# rx5808_vTup_0_4.net
KiCad netlist of a schematic drawn in EAGLE
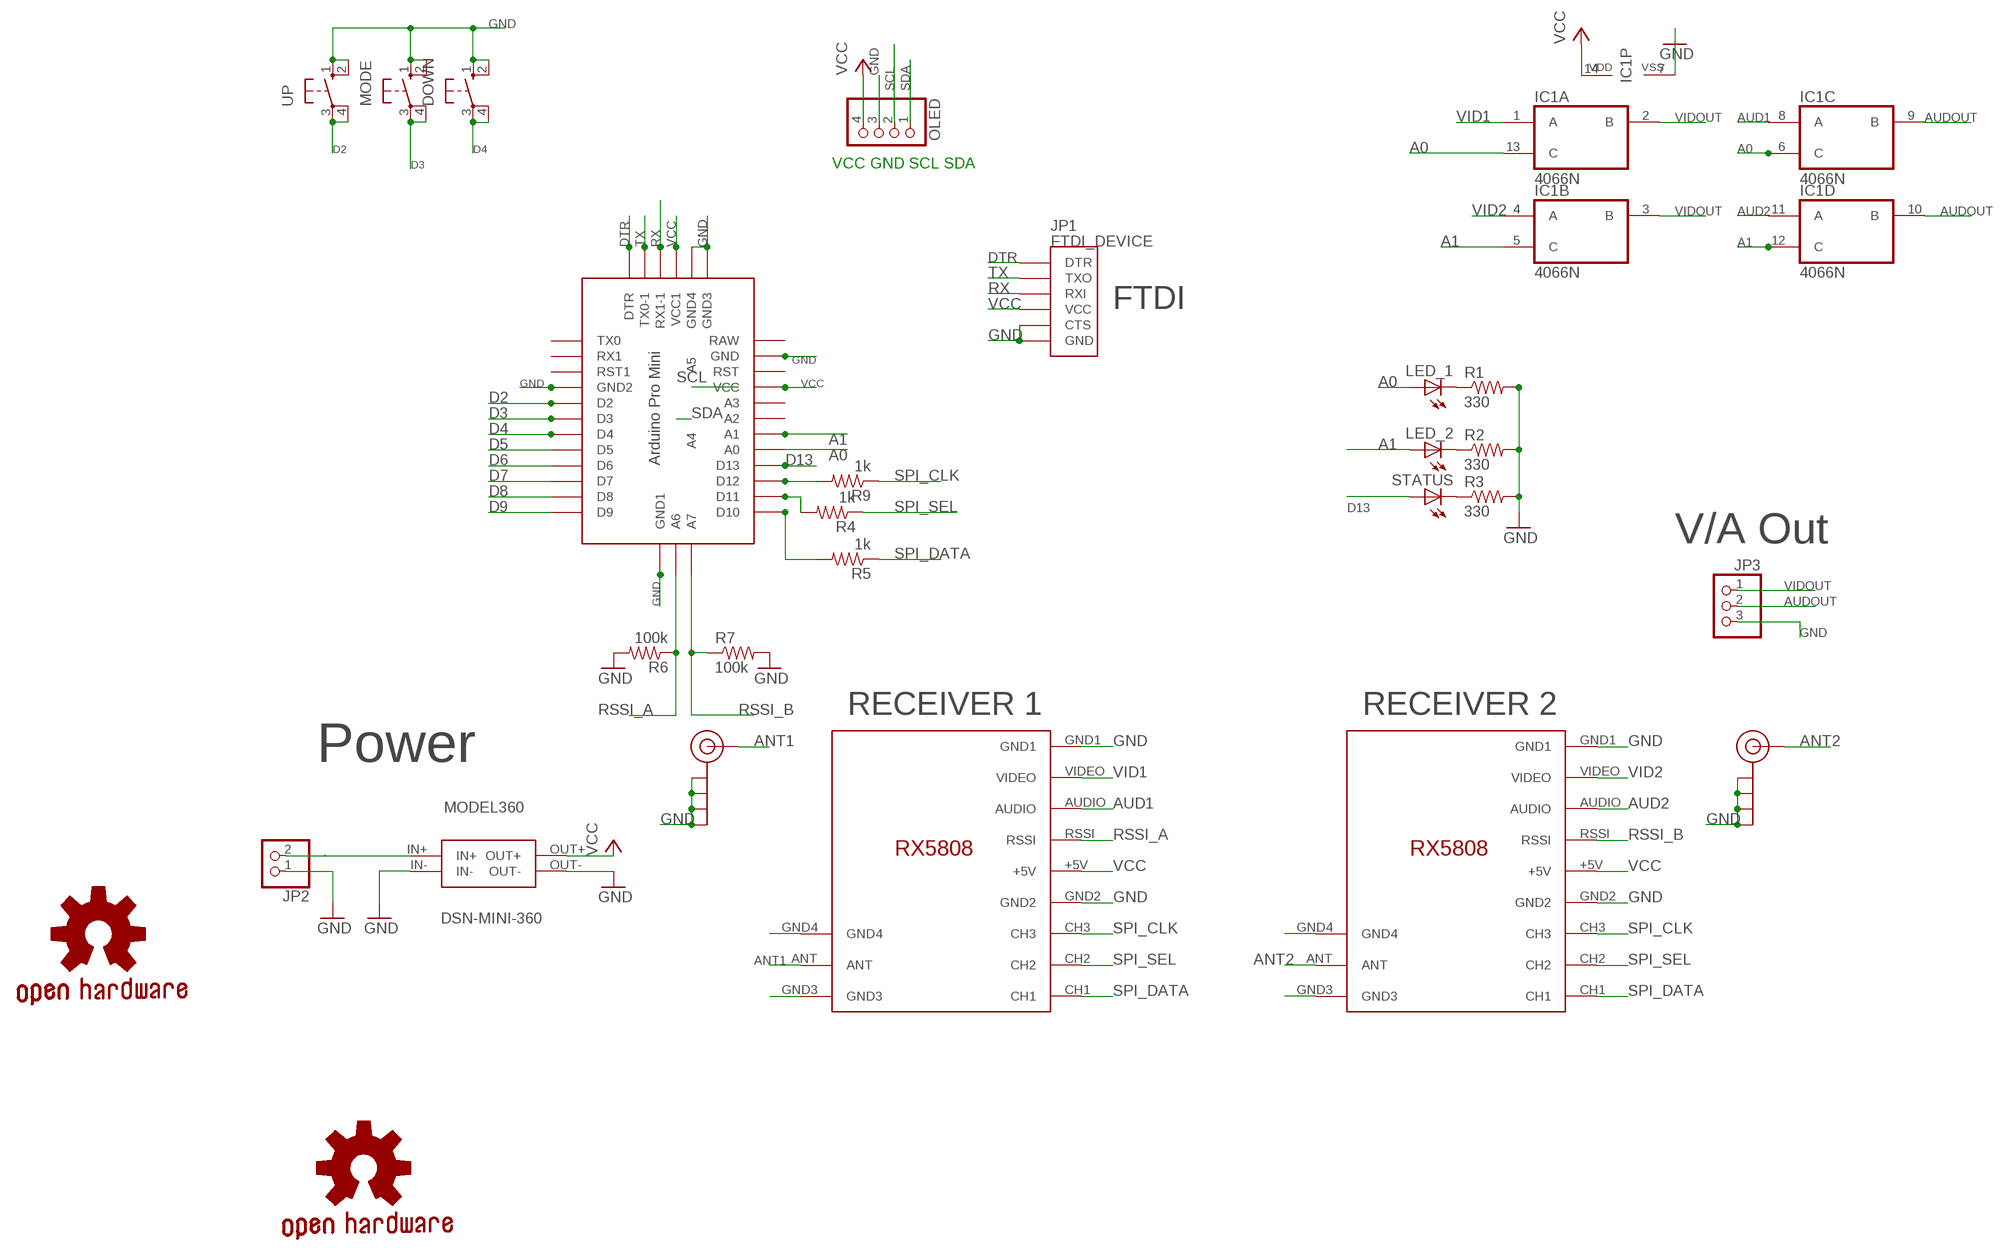
[diagram p0: schematic, sheet 1]

(export (version "E")
  (design (tool "Eeschema 10.0.6"))
  (components
    (comp (ref "ANT1")
      (value "SMA_EDGE")
      (footprint "eagle-import:SMA-EDGE")
      (libsource (lib "eagle-import") (part "SMA_EDGE"))
    )
    (comp (ref "ANT2")
      (value "SMA_EDGE")
      (footprint "eagle-import:SMA-EDGE")
      (libsource (lib "eagle-import") (part "SMA_EDGE"))
    )
    (comp (ref "DOWN")
      (value "10-XX")
      (footprint "eagle-import:B3F-10XX")
      (fields (field (name "MPN") "B3F-1000"))
      (libsource (lib "eagle-import") (part "10-XX"))
    )
    (comp (ref "DSN-MINI-360")
      (value "MODEL360")
      (footprint "eagle-import:MODEL360")
      (libsource (lib "eagle-import") (part "MODEL360"))
    )
    (comp (ref "GOLD_ORB_SM1")
      (value "OSHWLOGO_GOLD_ORB_LG")
      (footprint "eagle-import:OSHW0")
      (libsource (lib "eagle-import") (part "OSHWLOGO_GOLD_ORB_LG"))
    )
    (comp (ref "GOLD_ORB_SM2")
      (value "OSHWLOGO_GOLD_ORB_SM")
      (footprint "eagle-import:OSHW2")
      (libsource (lib "eagle-import") (part "OSHWLOGO_GOLD_ORB_SM"))
    )
    (comp (ref "IC1")
      (value "4066N")
      (footprint "eagle-import:DIL14")
      (libsource (lib "eagle-import") (part "4066N"))
    )
    (comp (ref "JP1")
      (value "FTDI_DEVICE")
      (footprint "eagle-import:FTDI_DEVICE_SIDE")
      (libsource (lib "eagle-import") (part "FTDI_DEVICE"))
    )
    (comp (ref "JP2")
      (value "PINHD-1X2")
      (footprint "eagle-import:1X02")
      (libsource (lib "eagle-import") (part "PINHD-1X2"))
    )
    (comp (ref "JP3")
      (value "PINHD-1X3")
      (footprint "eagle-import:1X03")
      (libsource (lib "eagle-import") (part "PINHD-1X3"))
    )
    (comp (ref "LED_1")
      (value "LED5MM")
      (footprint "eagle-import:LED5MM")
      (libsource (lib "eagle-import") (part "LED5MM"))
    )
    (comp (ref "LED_2")
      (value "LED5MM")
      (footprint "eagle-import:LED5MM")
      (libsource (lib "eagle-import") (part "LED5MM"))
    )
    (comp (ref "MODE")
      (value "10-XX")
      (footprint "eagle-import:B3F-10XX")
      (fields (field (name "MPN") "B3F-1000"))
      (libsource (lib "eagle-import") (part "10-XX"))
    )
    (comp (ref "OLED")
      (value "PINHD-1X4")
      (footprint "eagle-import:1X04")
      (libsource (lib "eagle-import") (part "PINHD-1X4"))
    )
    (comp (ref "R1")
      (value "330")
      (footprint "eagle-import:0207_7")
      (libsource (lib "eagle-import") (part "R-US_0207/7"))
    )
    (comp (ref "R2")
      (value "330")
      (footprint "eagle-import:0207_7")
      (libsource (lib "eagle-import") (part "R-US_0207/7"))
    )
    (comp (ref "R3")
      (value "330")
      (footprint "eagle-import:0207_7")
      (libsource (lib "eagle-import") (part "R-US_0207/7"))
    )
    (comp (ref "R4")
      (value "1k")
      (footprint "eagle-import:0207_7")
      (libsource (lib "eagle-import") (part "R-US_0207/7"))
    )
    (comp (ref "R5")
      (value "1k")
      (footprint "eagle-import:0207_7")
      (libsource (lib "eagle-import") (part "R-US_0207/7"))
    )
    (comp (ref "R6")
      (value "100k")
      (footprint "eagle-import:0207_7")
      (libsource (lib "eagle-import") (part "R-US_0207/7"))
    )
    (comp (ref "R7")
      (value "100k")
      (footprint "eagle-import:0207_7")
      (libsource (lib "eagle-import") (part "R-US_0207/7"))
    )
    (comp (ref "R9")
      (value "1k")
      (footprint "eagle-import:0207_7")
      (libsource (lib "eagle-import") (part "R-US_0207/7"))
    )
    (comp (ref "RECEIVER_A")
      (value "RX5808_A")
      (footprint "eagle-import:RX5808")
      (libsource (lib "eagle-import") (part "RX5808"))
    )
    (comp (ref "RECEIVER_B")
      (value "RX5808_B")
      (footprint "eagle-import:RX5808")
      (libsource (lib "eagle-import") (part "RX5808"))
    )
    (comp (ref "STATUS")
      (value "LED5MM")
      (footprint "eagle-import:LED5MM")
      (libsource (lib "eagle-import") (part "LED5MM"))
    )
    (comp (ref "U$1")
      (value "Pro Mini")
      (footprint "eagle-import:ABK-PRO-MINI")
      (libsource (lib "eagle-import") (part "ABK-PRO-MINI"))
    )
    (comp (ref "UP")
      (value "10-XX")
      (footprint "eagle-import:B3F-10XX")
      (fields (field (name "MPN") "B3F-1000"))
      (libsource (lib "eagle-import") (part "10-XX"))
    )
  )
  (nets
    (net (code "1") (name "/A0") (class "Default")
      (node (ref "IC1") (pin "13") (pinfunction "C_13") (pintype "input"))
      (node (ref "IC1") (pin "6") (pinfunction "C_6") (pintype "input"))
      (node (ref "LED_1") (pin "A") (pinfunction "A_A") (pintype "passive"))
      (node (ref "U$1") (pin "A0") (pinfunction "A0_A0") (pintype "bidirectional"))
    )
    (net (code "2") (name "/A1") (class "Default")
      (node (ref "IC1") (pin "12") (pinfunction "C_12") (pintype "input"))
      (node (ref "IC1") (pin "5") (pinfunction "C_5") (pintype "input"))
      (node (ref "LED_2") (pin "A") (pinfunction "A_A") (pintype "passive"))
      (node (ref "U$1") (pin "A1") (pinfunction "A1_A1") (pintype "bidirectional"))
    )
    (net (code "3") (name "/ANT1") (class "Default")
      (node (ref "ANT1") (pin "SIG") (pinfunction "SIGNAL_SIG") (pintype "bidirectional"))
      (node (ref "RECEIVER_A") (pin "ANT") (pinfunction "ANT_ANT") (pintype "bidirectional"))
    )
    (net (code "4") (name "/ANT2") (class "Default")
      (node (ref "ANT2") (pin "SIG") (pinfunction "SIGNAL_SIG") (pintype "bidirectional"))
      (node (ref "RECEIVER_B") (pin "ANT") (pinfunction "ANT_ANT") (pintype "bidirectional"))
    )
    (net (code "5") (name "/AUD1") (class "Default")
      (node (ref "IC1") (pin "8") (pinfunction "A_8") (pintype "tri_state"))
      (node (ref "RECEIVER_A") (pin "AUDIO") (pinfunction "AUDIO_AUDIO") (pintype "bidirectional"))
    )
    (net (code "6") (name "/AUD2") (class "Default")
      (node (ref "IC1") (pin "11") (pinfunction "A_11") (pintype "tri_state"))
      (node (ref "RECEIVER_B") (pin "AUDIO") (pinfunction "AUDIO_AUDIO") (pintype "bidirectional"))
    )
    (net (code "7") (name "/AUDOUT") (class "Default")
      (node (ref "IC1") (pin "10") (pinfunction "B_10") (pintype "tri_state"))
      (node (ref "IC1") (pin "9") (pinfunction "B_9") (pintype "tri_state"))
      (node (ref "JP3") (pin "2") (pinfunction "2_2") (pintype "passive"))
    )
    (net (code "8") (name "/D2") (class "Default")
      (node (ref "U$1") (pin "D2") (pinfunction "D2_D2") (pintype "bidirectional"))
      (node (ref "UP") (pin "3") (pinfunction "P_3") (pintype "passive"))
      (node (ref "UP") (pin "4") (pinfunction "P1_4") (pintype "passive"))
    )
    (net (code "9") (name "/D3") (class "Default")
      (node (ref "MODE") (pin "3") (pinfunction "P_3") (pintype "passive"))
      (node (ref "MODE") (pin "4") (pinfunction "P1_4") (pintype "passive"))
      (node (ref "U$1") (pin "D3") (pinfunction "D3_D3") (pintype "bidirectional"))
    )
    (net (code "10") (name "/D4") (class "Default")
      (node (ref "DOWN") (pin "3") (pinfunction "P_3") (pintype "passive"))
      (node (ref "DOWN") (pin "4") (pinfunction "P1_4") (pintype "passive"))
      (node (ref "U$1") (pin "D4") (pinfunction "D4_D4") (pintype "bidirectional"))
    )
    (net (code "11") (name "/D5") (class "Default")
      (node (ref "U$1") (pin "D5") (pinfunction "D5_D5") (pintype "bidirectional"))
    )
    (net (code "12") (name "/D6") (class "Default")
      (node (ref "U$1") (pin "D6") (pinfunction "D6_D6") (pintype "bidirectional"))
    )
    (net (code "13") (name "/D7") (class "Default")
      (node (ref "U$1") (pin "D7") (pinfunction "D7_D7") (pintype "bidirectional"))
    )
    (net (code "14") (name "/D8") (class "Default")
      (node (ref "U$1") (pin "D8") (pinfunction "D8_D8") (pintype "bidirectional"))
    )
    (net (code "15") (name "/D9") (class "Default")
      (node (ref "U$1") (pin "D9") (pinfunction "D9_D9") (pintype "bidirectional"))
    )
    (net (code "16") (name "/D13") (class "Default")
      (node (ref "STATUS") (pin "A") (pinfunction "A_A") (pintype "passive"))
      (node (ref "U$1") (pin "D13") (pinfunction "D13_D13") (pintype "bidirectional"))
    )
    (net (code "17") (name "/DTR") (class "Default")
      (node (ref "JP1") (pin "P$1") (pinfunction "DTR_P$1") (pintype "bidirectional"))
      (node (ref "U$1") (pin "GND2") (pinfunction "DTR_GND2") (pintype "bidirectional"))
    )
    (net (code "18") (name "/RSSI_A") (class "Default")
      (node (ref "R6") (pin "1") (pinfunction "1_1") (pintype "passive"))
      (node (ref "RECEIVER_A") (pin "RSSI") (pinfunction "RSSI_RSSI") (pintype "bidirectional"))
      (node (ref "U$1") (pin "A6") (pinfunction "A6_A6") (pintype "bidirectional"))
    )
    (net (code "19") (name "/RSSI_B") (class "Default")
      (node (ref "R7") (pin "1") (pinfunction "1_1") (pintype "passive"))
      (node (ref "RECEIVER_B") (pin "RSSI") (pinfunction "RSSI_RSSI") (pintype "bidirectional"))
      (node (ref "U$1") (pin "A7") (pinfunction "A7_A7") (pintype "bidirectional"))
    )
    (net (code "20") (name "/RX") (class "Default")
      (node (ref "JP1") (pin "P$3") (pinfunction "RXI_P$3") (pintype "bidirectional"))
      (node (ref "U$1") (pin "VCC1") (pinfunction "RX1-1_VCC1") (pintype "bidirectional"))
    )
    (net (code "21") (name "/SCL") (class "Default")
      (node (ref "OLED") (pin "2") (pinfunction "2_2") (pintype "passive"))
      (node (ref "U$1") (pin "A5") (pinfunction "A5_A5") (pintype "bidirectional"))
    )
    (net (code "22") (name "/SDA") (class "Default")
      (node (ref "OLED") (pin "1") (pinfunction "1_1") (pintype "passive"))
      (node (ref "U$1") (pin "A4") (pinfunction "A4_A4") (pintype "bidirectional"))
    )
    (net (code "23") (name "/SPI_CLK") (class "Default")
      (node (ref "R9") (pin "1") (pinfunction "1_1") (pintype "passive"))
      (node (ref "RECEIVER_A") (pin "CH3") (pinfunction "CH3_CH3") (pintype "bidirectional"))
      (node (ref "RECEIVER_B") (pin "CH3") (pinfunction "CH3_CH3") (pintype "bidirectional"))
    )
    (net (code "24") (name "/SPI_DATA") (class "Default")
      (node (ref "R5") (pin "1") (pinfunction "1_1") (pintype "passive"))
      (node (ref "RECEIVER_A") (pin "CH1") (pinfunction "CH1_CH1") (pintype "bidirectional"))
      (node (ref "RECEIVER_B") (pin "CH1") (pinfunction "CH1_CH1") (pintype "bidirectional"))
    )
    (net (code "25") (name "/SPI_SEL") (class "Default")
      (node (ref "R4") (pin "1") (pinfunction "1_1") (pintype "passive"))
      (node (ref "RECEIVER_A") (pin "CH2") (pinfunction "CH2_CH2") (pintype "bidirectional"))
      (node (ref "RECEIVER_B") (pin "CH2") (pinfunction "CH2_CH2") (pintype "bidirectional"))
    )
    (net (code "26") (name "/TX") (class "Default")
      (node (ref "JP1") (pin "P$2") (pinfunction "TXO_P$2") (pintype "bidirectional"))
      (node (ref "U$1") (pin "GND3") (pinfunction "TX0-1_GND3") (pintype "bidirectional"))
    )
    (net (code "28") (name "/VID1") (class "Default")
      (node (ref "IC1") (pin "1") (pinfunction "A_1") (pintype "tri_state"))
      (node (ref "RECEIVER_A") (pin "VIDEO") (pinfunction "VIDEO_VIDEO") (pintype "bidirectional"))
    )
    (net (code "29") (name "/VID2") (class "Default")
      (node (ref "IC1") (pin "4") (pinfunction "A_4") (pintype "tri_state"))
      (node (ref "RECEIVER_B") (pin "VIDEO") (pinfunction "VIDEO_VIDEO") (pintype "bidirectional"))
    )
    (net (code "30") (name "/VIDOUT") (class "Default")
      (node (ref "IC1") (pin "2") (pinfunction "B_2") (pintype "tri_state"))
      (node (ref "IC1") (pin "3") (pinfunction "B_3") (pintype "tri_state"))
      (node (ref "JP3") (pin "1") (pinfunction "1_1") (pintype "passive"))
    )
    (net (code "31") (name "GND") (class "Default")
      (node (ref "ANT1") (pin "GND@0") (pinfunction "GND_GND@0") (pintype "bidirectional"))
      (node (ref "ANT1") (pin "GND@1") (pinfunction "GND_GND@1") (pintype "bidirectional"))
      (node (ref "ANT1") (pin "GND@2") (pinfunction "GND_GND@2") (pintype "bidirectional"))
      (node (ref "ANT1") (pin "GND@3") (pinfunction "GND_GND@3") (pintype "bidirectional"))
      (node (ref "ANT2") (pin "GND@0") (pinfunction "GND_GND@0") (pintype "bidirectional"))
      (node (ref "ANT2") (pin "GND@1") (pinfunction "GND_GND@1") (pintype "bidirectional"))
      (node (ref "ANT2") (pin "GND@2") (pinfunction "GND_GND@2") (pintype "bidirectional"))
      (node (ref "ANT2") (pin "GND@3") (pinfunction "GND_GND@3") (pintype "bidirectional"))
      (node (ref "DOWN") (pin "1") (pinfunction "S_1") (pintype "passive"))
      (node (ref "DOWN") (pin "2") (pinfunction "S1_2") (pintype "passive"))
      (node (ref "DSN-MINI-360") (pin "IN-") (pinfunction "IN-_IN-") (pintype "bidirectional"))
      (node (ref "DSN-MINI-360") (pin "OUT-") (pinfunction "OUT-_OUT-") (pintype "bidirectional"))
      (node (ref "IC1") (pin "7") (pinfunction "VSS_7") (pintype "power_in"))
      (node (ref "JP1") (pin "P$5") (pinfunction "CTS_P$5") (pintype "bidirectional"))
      (node (ref "JP1") (pin "P$6") (pinfunction "GND_P$6") (pintype "bidirectional"))
      (node (ref "JP2") (pin "1") (pinfunction "1_1") (pintype "passive"))
      (node (ref "JP3") (pin "3") (pinfunction "3_3") (pintype "passive"))
      (node (ref "MODE") (pin "1") (pinfunction "S_1") (pintype "passive"))
      (node (ref "MODE") (pin "2") (pinfunction "S1_2") (pintype "passive"))
      (node (ref "OLED") (pin "3") (pinfunction "3_3") (pintype "passive"))
      (node (ref "R1") (pin "2") (pinfunction "2_2") (pintype "passive"))
      (node (ref "R2") (pin "2") (pinfunction "2_2") (pintype "passive"))
      (node (ref "R3") (pin "2") (pinfunction "2_2") (pintype "passive"))
      (node (ref "R6") (pin "2") (pinfunction "2_2") (pintype "passive"))
      (node (ref "R7") (pin "2") (pinfunction "2_2") (pintype "passive"))
      (node (ref "RECEIVER_A") (pin "GND1") (pinfunction "GND1_GND1") (pintype "bidirectional"))
      (node (ref "RECEIVER_A") (pin "GND2") (pinfunction "GND2_GND2") (pintype "bidirectional"))
      (node (ref "RECEIVER_A") (pin "GND3") (pinfunction "GND3_GND3") (pintype "bidirectional"))
      (node (ref "RECEIVER_A") (pin "GND4") (pinfunction "GND4_GND4") (pintype "bidirectional"))
      (node (ref "RECEIVER_B") (pin "GND1") (pinfunction "GND1_GND1") (pintype "bidirectional"))
      (node (ref "RECEIVER_B") (pin "GND2") (pinfunction "GND2_GND2") (pintype "bidirectional"))
      (node (ref "RECEIVER_B") (pin "GND3") (pinfunction "GND3_GND3") (pintype "bidirectional"))
      (node (ref "RECEIVER_B") (pin "GND4") (pinfunction "GND4_GND4") (pintype "bidirectional"))
      (node (ref "U$1") (pin "DTR") (pinfunction "GND3_DTR") (pintype "bidirectional"))
      (node (ref "U$1") (pin "GND") (pinfunction "GND_GND") (pintype "bidirectional"))
      (node (ref "U$1") (pin "GND1") (pinfunction "GND2_GND1") (pintype "bidirectional"))
      (node (ref "U$1") (pin "GND4") (pinfunction "GND1_GND4") (pintype "bidirectional"))
      (node (ref "U$1") (pin "TX0-1") (pinfunction "GND4_TX0-1") (pintype "bidirectional"))
      (node (ref "UP") (pin "1") (pinfunction "S_1") (pintype "passive"))
      (node (ref "UP") (pin "2") (pinfunction "S1_2") (pintype "passive"))
    )
    (net (code "32") (name "Net-(DSN-MINI-360-PadIN+)") (class "Default")
      (node (ref "DSN-MINI-360") (pin "IN+") (pinfunction "IN+_IN+") (pintype "bidirectional"))
      (node (ref "JP2") (pin "2") (pinfunction "2_2") (pintype "passive"))
    )
    (net (code "33") (name "Net-(LED_1-C)") (class "Default")
      (node (ref "LED_1") (pin "K") (pinfunction "C_K") (pintype "passive"))
      (node (ref "R1") (pin "1") (pinfunction "1_1") (pintype "passive"))
    )
    (net (code "34") (name "Net-(LED_2-C)") (class "Default")
      (node (ref "LED_2") (pin "K") (pinfunction "C_K") (pintype "passive"))
      (node (ref "R2") (pin "1") (pinfunction "1_1") (pintype "passive"))
    )
    (net (code "35") (name "Net-(R4-Pad2)") (class "Default")
      (node (ref "R4") (pin "2") (pinfunction "2_2") (pintype "passive"))
      (node (ref "U$1") (pin "D11") (pinfunction "D11_D11") (pintype "bidirectional"))
    )
    (net (code "36") (name "Net-(R5-Pad2)") (class "Default")
      (node (ref "R5") (pin "2") (pinfunction "2_2") (pintype "passive"))
      (node (ref "U$1") (pin "D10") (pinfunction "D10_D10") (pintype "bidirectional"))
    )
    (net (code "37") (name "Net-(R9-Pad2)") (class "Default")
      (node (ref "R9") (pin "2") (pinfunction "2_2") (pintype "passive"))
      (node (ref "U$1") (pin "D12") (pinfunction "D12_D12") (pintype "bidirectional"))
    )
    (net (code "38") (name "Net-(STATUS-C)") (class "Default")
      (node (ref "R3") (pin "1") (pinfunction "1_1") (pintype "passive"))
      (node (ref "STATUS") (pin "K") (pinfunction "C_K") (pintype "passive"))
    )
    (net (code "39") (name "VCC") (class "Default")
      (node (ref "DSN-MINI-360") (pin "OUT+") (pinfunction "OUT+_OUT+") (pintype "bidirectional"))
      (node (ref "IC1") (pin "14") (pinfunction "VDD_14") (pintype "power_in"))
      (node (ref "JP1") (pin "P$4") (pinfunction "VCC_P$4") (pintype "bidirectional"))
      (node (ref "OLED") (pin "4") (pinfunction "4_4") (pintype "passive"))
      (node (ref "RECEIVER_A") (pin "+5V") (pinfunction "+5V_+5V") (pintype "bidirectional"))
      (node (ref "RECEIVER_B") (pin "+5V") (pinfunction "+5V_+5V") (pintype "bidirectional"))
      (node (ref "U$1") (pin "RX1-1") (pinfunction "VCC1_RX1-1") (pintype "bidirectional"))
      (node (ref "U$1") (pin "VCC") (pinfunction "VCC_VCC") (pintype "bidirectional"))
    )
    (net (code "40") (name "unconnected-(U$1-PadA2)") (class "Default")
      (node (ref "U$1") (pin "A2") (pinfunction "A2_A2") (pintype "bidirectional"))
    )
    (net (code "41") (name "unconnected-(U$1-PadA3)") (class "Default")
      (node (ref "U$1") (pin "A3") (pinfunction "A3_A3") (pintype "bidirectional"))
    )
    (net (code "42") (name "unconnected-(U$1-PadRAW)") (class "Default")
      (node (ref "U$1") (pin "RAW") (pinfunction "RAW_RAW") (pintype "bidirectional"))
    )
    (net (code "43") (name "unconnected-(U$1-PadRST)") (class "Default")
      (node (ref "U$1") (pin "RST") (pinfunction "RST_RST") (pintype "bidirectional"))
    )
    (net (code "44") (name "unconnected-(U$1-PadRST1)") (class "Default")
      (node (ref "U$1") (pin "RST1") (pinfunction "RST1_RST1") (pintype "bidirectional"))
    )
    (net (code "45") (name "unconnected-(U$1-PadRX1)") (class "Default")
      (node (ref "U$1") (pin "RX1") (pinfunction "RX1_RX1") (pintype "bidirectional"))
    )
    (net (code "46") (name "unconnected-(U$1-PadTX0)") (class "Default")
      (node (ref "U$1") (pin "TX0") (pinfunction "TX0_TX0") (pintype "bidirectional"))
    )
  )
)
